# THS788_3.net
KiCad netlist of a schematic drawn in Altium Designer
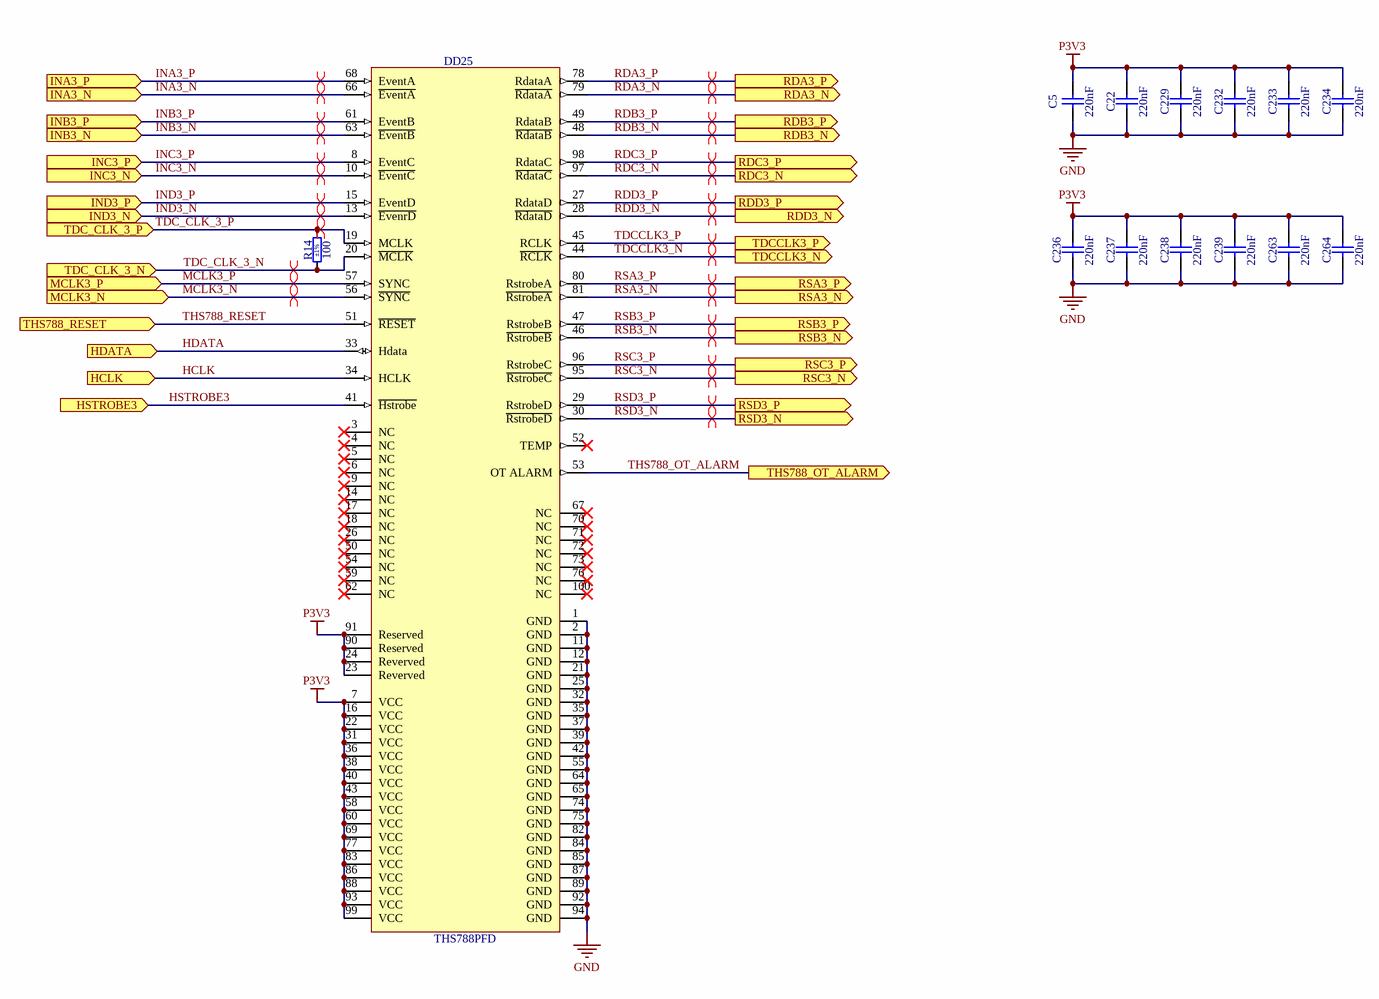
[diagram p0: THS788_3.SchDoc]

(export (version "E")
  (design (tool "Eeschema 10.0.6"))
  (components
    (comp (ref "C5")
      (value "220nF")
      (footprint "CAPC2012X135N")
      (description "Non-polarised capacitor")
      (fields
        (field (name "PART NUMBER") "CC0805_220NF_50V_10%_X7R")
        (field (name "VOLTAGE") "50V")
        (field (name "AUTHOR") "CERN DEM JLC")
      )
      (libsource (lib "Capacitors") (part "Capacitor - non polarized"))
    )
    (comp (ref "C22")
      (value "220nF")
      (footprint "CAPC2012X135N")
      (description "Non-polarised capacitor")
      (fields
        (field (name "PART NUMBER") "CC0805_220NF_50V_10%_X7R")
        (field (name "VOLTAGE") "50V")
        (field (name "AUTHOR") "CERN DEM JLC")
      )
      (libsource (lib "Capacitors") (part "Capacitor - non polarized"))
    )
    (comp (ref "C229")
      (value "220nF")
      (footprint "CAPC2012X135N")
      (description "Non-polarised capacitor")
      (fields
        (field (name "PART NUMBER") "CC0805_220NF_50V_10%_X7R")
        (field (name "VOLTAGE") "50V")
        (field (name "AUTHOR") "CERN DEM JLC")
      )
      (libsource (lib "Capacitors") (part "Capacitor - non polarized"))
    )
    (comp (ref "C232")
      (value "220nF")
      (footprint "CAPC2012X135N")
      (description "Non-polarised capacitor")
      (fields
        (field (name "PART NUMBER") "CC0805_220NF_50V_10%_X7R")
        (field (name "VOLTAGE") "50V")
        (field (name "AUTHOR") "CERN DEM JLC")
      )
      (libsource (lib "Capacitors") (part "Capacitor - non polarized"))
    )
    (comp (ref "C233")
      (value "220nF")
      (footprint "CAPC2012X135N")
      (description "Non-polarised capacitor")
      (fields
        (field (name "PART NUMBER") "CC0805_220NF_50V_10%_X7R")
        (field (name "VOLTAGE") "50V")
        (field (name "AUTHOR") "CERN DEM JLC")
      )
      (libsource (lib "Capacitors") (part "Capacitor - non polarized"))
    )
    (comp (ref "C234")
      (value "220nF")
      (footprint "CAPC2012X135N")
      (description "Non-polarised capacitor")
      (fields
        (field (name "PART NUMBER") "CC0805_220NF_50V_10%_X7R")
        (field (name "VOLTAGE") "50V")
        (field (name "AUTHOR") "CERN DEM JLC")
      )
      (libsource (lib "Capacitors") (part "Capacitor - non polarized"))
    )
    (comp (ref "C236")
      (value "220nF")
      (footprint "CAPC2012X135N")
      (description "Non-polarised capacitor")
      (fields
        (field (name "PART NUMBER") "CC0805_220NF_50V_10%_X7R")
        (field (name "VOLTAGE") "50V")
        (field (name "AUTHOR") "CERN DEM JLC")
      )
      (libsource (lib "Capacitors") (part "Capacitor - non polarized"))
    )
    (comp (ref "C237")
      (value "220nF")
      (footprint "CAPC2012X135N")
      (description "Non-polarised capacitor")
      (fields
        (field (name "PART NUMBER") "CC0805_220NF_50V_10%_X7R")
        (field (name "VOLTAGE") "50V")
        (field (name "AUTHOR") "CERN DEM JLC")
      )
      (libsource (lib "Capacitors") (part "Capacitor - non polarized"))
    )
    (comp (ref "C238")
      (value "220nF")
      (footprint "CAPC2012X135N")
      (description "Non-polarised capacitor")
      (fields
        (field (name "PART NUMBER") "CC0805_220NF_50V_10%_X7R")
        (field (name "VOLTAGE") "50V")
        (field (name "AUTHOR") "CERN DEM JLC")
      )
      (libsource (lib "Capacitors") (part "Capacitor - non polarized"))
    )
    (comp (ref "C239")
      (value "220nF")
      (footprint "CAPC2012X135N")
      (description "Non-polarised capacitor")
      (fields
        (field (name "PART NUMBER") "CC0805_220NF_50V_10%_X7R")
        (field (name "VOLTAGE") "50V")
        (field (name "AUTHOR") "CERN DEM JLC")
      )
      (libsource (lib "Capacitors") (part "Capacitor - non polarized"))
    )
    (comp (ref "C263")
      (value "220nF")
      (footprint "CAPC2012X135N")
      (description "Non-polarised capacitor")
      (fields
        (field (name "PART NUMBER") "CC0805_220NF_50V_10%_X7R")
        (field (name "VOLTAGE") "50V")
        (field (name "AUTHOR") "CERN DEM JLC")
      )
      (libsource (lib "Capacitors") (part "Capacitor - non polarized"))
    )
    (comp (ref "C264")
      (value "220nF")
      (footprint "CAPC2012X135N")
      (description "Non-polarised capacitor")
      (fields
        (field (name "PART NUMBER") "CC0805_220NF_50V_10%_X7R")
        (field (name "VOLTAGE") "50V")
        (field (name "AUTHOR") "CERN DEM JLC")
      )
      (libsource (lib "Capacitors") (part "Capacitor - non polarized"))
    )
    (comp (ref "DD25")
      (value "THS788PFD")
      (footprint "TEXAS_PFD (S-PQFP-G100)")
      (description "Quad-Channel Time Measurement Unit (TMU)")
      (fields (field (name "MANUFACTURER") "TEXAS INSTRUMENTS") (field (name "AUTHOR") "CERN DEM HF"))
      (libsource (lib "ICs And Semiconductors") (part "THS788PFD"))
    )
    (comp (ref "R14")
      (value "100")
      (footprint "RESC1608X55N")
      (description "Resistor - 1%")
      (fields
        (field (name "TOLERANCE") "±1%")
        (field (name "PART NUMBER") "R0603_100R_1%_0.1W_100PPM")
        (field (name "POWER") "0.1W")
        (field (name "AUTHOR") "CERN DEM JLC")
      )
      (libsource (lib "Resistors") (part "Resistor - 1%"))
    )
  )
  (nets
    (net (code "1") (name "/HCLK") (class "Default")
      (node (ref "DD25") (pin "34") (pinfunction "HCLK_34") (pintype "input"))
    )
    (net (code "2") (name "/HDATA") (class "Default")
      (node (ref "DD25") (pin "33") (pinfunction "Hdata_33") (pintype "bidirectional"))
    )
    (net (code "3") (name "/HSTROBE3") (class "Default")
      (node (ref "DD25") (pin "41") (pinfunction "~{Hstrobe}_41") (pintype "input"))
    )
    (net (code "4") (name "/INA3_N") (class "Default")
      (node (ref "DD25") (pin "66") (pinfunction "~{EventA}_66") (pintype "input"))
    )
    (net (code "5") (name "/INA3_P") (class "Default")
      (node (ref "DD25") (pin "68") (pinfunction "EventA_68") (pintype "input"))
    )
    (net (code "6") (name "/INB3_N") (class "Default")
      (node (ref "DD25") (pin "63") (pinfunction "~{EventB}_63") (pintype "input"))
    )
    (net (code "7") (name "/INB3_P") (class "Default")
      (node (ref "DD25") (pin "61") (pinfunction "EventB_61") (pintype "input"))
    )
    (net (code "8") (name "/INC3_N") (class "Default")
      (node (ref "DD25") (pin "10") (pinfunction "~{EventC}_10") (pintype "input"))
    )
    (net (code "9") (name "/INC3_P") (class "Default")
      (node (ref "DD25") (pin "8") (pinfunction "EventC_8") (pintype "input"))
    )
    (net (code "10") (name "/IND3_N") (class "Default")
      (node (ref "DD25") (pin "13") (pinfunction "~{EvenrD}_13") (pintype "input"))
    )
    (net (code "11") (name "/IND3_P") (class "Default")
      (node (ref "DD25") (pin "15") (pinfunction "EventD_15") (pintype "input"))
    )
    (net (code "12") (name "/MCLK3_N") (class "Default")
      (node (ref "DD25") (pin "56") (pinfunction "~{SYNC}_56") (pintype "input"))
    )
    (net (code "13") (name "/MCLK3_P") (class "Default")
      (node (ref "DD25") (pin "57") (pinfunction "SYNC_57") (pintype "input"))
    )
    (net (code "14") (name "/RDA3_N") (class "Default")
      (node (ref "DD25") (pin "79") (pinfunction "~{RdataA}_79") (pintype "output"))
    )
    (net (code "15") (name "/RDA3_P") (class "Default")
      (node (ref "DD25") (pin "78") (pinfunction "RdataA_78") (pintype "output"))
    )
    (net (code "16") (name "/RDB3_N") (class "Default")
      (node (ref "DD25") (pin "48") (pinfunction "~{RdataB}_48") (pintype "output"))
    )
    (net (code "17") (name "/RDB3_P") (class "Default")
      (node (ref "DD25") (pin "49") (pinfunction "RdataB_49") (pintype "output"))
    )
    (net (code "18") (name "/RDC3_N") (class "Default")
      (node (ref "DD25") (pin "97") (pinfunction "~{RdataC}_97") (pintype "output"))
    )
    (net (code "19") (name "/RDC3_P") (class "Default")
      (node (ref "DD25") (pin "98") (pinfunction "RdataC_98") (pintype "output"))
    )
    (net (code "20") (name "/RDD3_N") (class "Default")
      (node (ref "DD25") (pin "28") (pinfunction "~{RdataD}_28") (pintype "output"))
    )
    (net (code "21") (name "/RDD3_P") (class "Default")
      (node (ref "DD25") (pin "27") (pinfunction "RdataD_27") (pintype "output"))
    )
    (net (code "22") (name "/RSA3_N") (class "Default")
      (node (ref "DD25") (pin "81") (pinfunction "~{RstrobeA}_81") (pintype "output"))
    )
    (net (code "23") (name "/RSA3_P") (class "Default")
      (node (ref "DD25") (pin "80") (pinfunction "RstrobeA_80") (pintype "output"))
    )
    (net (code "24") (name "/RSB3_N") (class "Default")
      (node (ref "DD25") (pin "46") (pinfunction "~{RstrobeB}_46") (pintype "output"))
    )
    (net (code "25") (name "/RSB3_P") (class "Default")
      (node (ref "DD25") (pin "47") (pinfunction "RstrobeB_47") (pintype "output"))
    )
    (net (code "26") (name "/RSC3_N") (class "Default")
      (node (ref "DD25") (pin "95") (pinfunction "~{RstrobeC}_95") (pintype "output"))
    )
    (net (code "27") (name "/RSC3_P") (class "Default")
      (node (ref "DD25") (pin "96") (pinfunction "RstrobeC_96") (pintype "output"))
    )
    (net (code "28") (name "/RSD3_N") (class "Default")
      (node (ref "DD25") (pin "30") (pinfunction "~{RstrobeD}_30") (pintype "output"))
    )
    (net (code "29") (name "/RSD3_P") (class "Default")
      (node (ref "DD25") (pin "29") (pinfunction "RstrobeD_29") (pintype "output"))
    )
    (net (code "30") (name "/TDCCLK3_N") (class "Default")
      (node (ref "DD25") (pin "44") (pinfunction "~{RCLK}_44") (pintype "output"))
    )
    (net (code "31") (name "/TDCCLK3_P") (class "Default")
      (node (ref "DD25") (pin "45") (pinfunction "RCLK_45") (pintype "output"))
    )
    (net (code "32") (name "/TDC_CLK_3_N") (class "Default")
      (node (ref "DD25") (pin "20") (pinfunction "~{MCLK}_20") (pintype "input"))
      (node (ref "R14") (pin "1") (pinfunction "1_1") (pintype "passive"))
    )
    (net (code "33") (name "/TDC_CLK_3_P") (class "Default")
      (node (ref "DD25") (pin "19") (pinfunction "MCLK_19") (pintype "input"))
      (node (ref "R14") (pin "2") (pinfunction "2_2") (pintype "passive"))
    )
    (net (code "34") (name "/THS788_OT_ALARM") (class "Default")
      (node (ref "DD25") (pin "53") (pinfunction "OT_ALARM_53") (pintype "output"))
    )
    (net (code "35") (name "/THS788_RESET") (class "Default")
      (node (ref "DD25") (pin "51") (pinfunction "~{RESET}_51") (pintype "input"))
    )
    (net (code "36") (name "GND") (class "Default")
      (node (ref "C22") (pin "1") (pinfunction "1_1") (pintype "passive"))
      (node (ref "C229") (pin "1") (pinfunction "1_1") (pintype "passive"))
      (node (ref "C232") (pin "1") (pinfunction "1_1") (pintype "passive"))
      (node (ref "C233") (pin "1") (pinfunction "1_1") (pintype "passive"))
      (node (ref "C234") (pin "1") (pinfunction "1_1") (pintype "passive"))
      (node (ref "C236") (pin "1") (pinfunction "1_1") (pintype "passive"))
      (node (ref "C237") (pin "1") (pinfunction "1_1") (pintype "passive"))
      (node (ref "C238") (pin "1") (pinfunction "1_1") (pintype "passive"))
      (node (ref "C239") (pin "1") (pinfunction "1_1") (pintype "passive"))
      (node (ref "C263") (pin "1") (pinfunction "1_1") (pintype "passive"))
      (node (ref "C264") (pin "1") (pinfunction "1_1") (pintype "passive"))
      (node (ref "C5") (pin "1") (pinfunction "1_1") (pintype "passive"))
      (node (ref "DD25") (pin "1") (pinfunction "GND_1") (pintype "power_in"))
      (node (ref "DD25") (pin "11") (pinfunction "GND_11") (pintype "power_in"))
      (node (ref "DD25") (pin "12") (pinfunction "GND_12") (pintype "power_in"))
      (node (ref "DD25") (pin "2") (pinfunction "GND_2") (pintype "power_in"))
      (node (ref "DD25") (pin "21") (pinfunction "GND_21") (pintype "power_in"))
      (node (ref "DD25") (pin "25") (pinfunction "GND_25") (pintype "power_in"))
      (node (ref "DD25") (pin "32") (pinfunction "GND_32") (pintype "power_in"))
      (node (ref "DD25") (pin "35") (pinfunction "GND_35") (pintype "power_in"))
      (node (ref "DD25") (pin "37") (pinfunction "GND_37") (pintype "power_in"))
      (node (ref "DD25") (pin "39") (pinfunction "GND_39") (pintype "power_in"))
      (node (ref "DD25") (pin "42") (pinfunction "GND_42") (pintype "power_in"))
      (node (ref "DD25") (pin "55") (pinfunction "GND_55") (pintype "power_in"))
      (node (ref "DD25") (pin "64") (pinfunction "GND_64") (pintype "power_in"))
      (node (ref "DD25") (pin "65") (pinfunction "GND_65") (pintype "power_in"))
      (node (ref "DD25") (pin "74") (pinfunction "GND_74") (pintype "power_in"))
      (node (ref "DD25") (pin "75") (pinfunction "GND_75") (pintype "power_in"))
      (node (ref "DD25") (pin "82") (pinfunction "GND_82") (pintype "power_in"))
      (node (ref "DD25") (pin "84") (pinfunction "GND_84") (pintype "power_in"))
      (node (ref "DD25") (pin "85") (pinfunction "GND_85") (pintype "power_in"))
      (node (ref "DD25") (pin "87") (pinfunction "GND_87") (pintype "power_in"))
      (node (ref "DD25") (pin "89") (pinfunction "GND_89") (pintype "power_in"))
      (node (ref "DD25") (pin "92") (pinfunction "GND_92") (pintype "power_in"))
      (node (ref "DD25") (pin "94") (pinfunction "GND_94") (pintype "power_in"))
    )
    (net (code "37") (name "P3V3") (class "Default")
      (node (ref "C22") (pin "2") (pinfunction "2_2") (pintype "passive"))
      (node (ref "C229") (pin "2") (pinfunction "2_2") (pintype "passive"))
      (node (ref "C232") (pin "2") (pinfunction "2_2") (pintype "passive"))
      (node (ref "C233") (pin "2") (pinfunction "2_2") (pintype "passive"))
      (node (ref "C234") (pin "2") (pinfunction "2_2") (pintype "passive"))
      (node (ref "C236") (pin "2") (pinfunction "2_2") (pintype "passive"))
      (node (ref "C237") (pin "2") (pinfunction "2_2") (pintype "passive"))
      (node (ref "C238") (pin "2") (pinfunction "2_2") (pintype "passive"))
      (node (ref "C239") (pin "2") (pinfunction "2_2") (pintype "passive"))
      (node (ref "C263") (pin "2") (pinfunction "2_2") (pintype "passive"))
      (node (ref "C264") (pin "2") (pinfunction "2_2") (pintype "passive"))
      (node (ref "C5") (pin "2") (pinfunction "2_2") (pintype "passive"))
      (node (ref "DD25") (pin "16") (pinfunction "VCC_16") (pintype "power_in"))
      (node (ref "DD25") (pin "22") (pinfunction "VCC_22") (pintype "power_in"))
      (node (ref "DD25") (pin "23") (pinfunction "Reverved_23") (pintype "passive"))
      (node (ref "DD25") (pin "24") (pinfunction "Reverved_24") (pintype "passive"))
      (node (ref "DD25") (pin "31") (pinfunction "VCC_31") (pintype "power_in"))
      (node (ref "DD25") (pin "36") (pinfunction "VCC_36") (pintype "power_in"))
      (node (ref "DD25") (pin "38") (pinfunction "VCC_38") (pintype "power_in"))
      (node (ref "DD25") (pin "40") (pinfunction "VCC_40") (pintype "power_in"))
      (node (ref "DD25") (pin "43") (pinfunction "VCC_43") (pintype "power_in"))
      (node (ref "DD25") (pin "58") (pinfunction "VCC_58") (pintype "power_in"))
      (node (ref "DD25") (pin "60") (pinfunction "VCC_60") (pintype "power_in"))
      (node (ref "DD25") (pin "69") (pinfunction "VCC_69") (pintype "power_in"))
      (node (ref "DD25") (pin "7") (pinfunction "VCC_7") (pintype "power_in"))
      (node (ref "DD25") (pin "77") (pinfunction "VCC_77") (pintype "power_in"))
      (node (ref "DD25") (pin "83") (pinfunction "VCC_83") (pintype "power_in"))
      (node (ref "DD25") (pin "86") (pinfunction "VCC_86") (pintype "power_in"))
      (node (ref "DD25") (pin "88") (pinfunction "VCC_88") (pintype "power_in"))
      (node (ref "DD25") (pin "90") (pinfunction "Reserved_90") (pintype "passive"))
      (node (ref "DD25") (pin "91") (pinfunction "Reserved_91") (pintype "passive"))
      (node (ref "DD25") (pin "93") (pinfunction "VCC_93") (pintype "power_in"))
      (node (ref "DD25") (pin "99") (pinfunction "VCC_99") (pintype "power_in"))
    )
    (net (code "38") (name "unconnected-(DD25-NC-Pad3)") (class "Default")
      (node (ref "DD25") (pin "3") (pinfunction "NC_3") (pintype "passive+no_connect"))
    )
    (net (code "39") (name "unconnected-(DD25-NC-Pad4)") (class "Default")
      (node (ref "DD25") (pin "4") (pinfunction "NC_4") (pintype "passive+no_connect"))
    )
    (net (code "40") (name "unconnected-(DD25-NC-Pad5)") (class "Default")
      (node (ref "DD25") (pin "5") (pinfunction "NC_5") (pintype "passive+no_connect"))
    )
    (net (code "41") (name "unconnected-(DD25-NC-Pad6)") (class "Default")
      (node (ref "DD25") (pin "6") (pinfunction "NC_6") (pintype "passive+no_connect"))
    )
    (net (code "42") (name "unconnected-(DD25-NC-Pad9)") (class "Default")
      (node (ref "DD25") (pin "9") (pinfunction "NC_9") (pintype "passive+no_connect"))
    )
    (net (code "43") (name "unconnected-(DD25-NC-Pad14)") (class "Default")
      (node (ref "DD25") (pin "14") (pinfunction "NC_14") (pintype "passive+no_connect"))
    )
    (net (code "44") (name "unconnected-(DD25-NC-Pad17)") (class "Default")
      (node (ref "DD25") (pin "17") (pinfunction "NC_17") (pintype "passive+no_connect"))
    )
    (net (code "45") (name "unconnected-(DD25-NC-Pad18)") (class "Default")
      (node (ref "DD25") (pin "18") (pinfunction "NC_18") (pintype "passive+no_connect"))
    )
    (net (code "46") (name "unconnected-(DD25-NC-Pad26)") (class "Default")
      (node (ref "DD25") (pin "26") (pinfunction "NC_26") (pintype "passive+no_connect"))
    )
    (net (code "47") (name "unconnected-(DD25-NC-Pad50)") (class "Default")
      (node (ref "DD25") (pin "50") (pinfunction "NC_50") (pintype "passive+no_connect"))
    )
    (net (code "48") (name "unconnected-(DD25-NC-Pad54)") (class "Default")
      (node (ref "DD25") (pin "54") (pinfunction "NC_54") (pintype "passive+no_connect"))
    )
    (net (code "49") (name "unconnected-(DD25-NC-Pad59)") (class "Default")
      (node (ref "DD25") (pin "59") (pinfunction "NC_59") (pintype "passive+no_connect"))
    )
    (net (code "50") (name "unconnected-(DD25-NC-Pad62)") (class "Default")
      (node (ref "DD25") (pin "62") (pinfunction "NC_62") (pintype "passive+no_connect"))
    )
    (net (code "51") (name "unconnected-(DD25-NC-Pad67)") (class "Default")
      (node (ref "DD25") (pin "67") (pinfunction "NC_67") (pintype "passive+no_connect"))
    )
    (net (code "52") (name "unconnected-(DD25-NC-Pad70)") (class "Default")
      (node (ref "DD25") (pin "70") (pinfunction "NC_70") (pintype "passive+no_connect"))
    )
    (net (code "53") (name "unconnected-(DD25-NC-Pad71)") (class "Default")
      (node (ref "DD25") (pin "71") (pinfunction "NC_71") (pintype "passive+no_connect"))
    )
    (net (code "54") (name "unconnected-(DD25-NC-Pad72)") (class "Default")
      (node (ref "DD25") (pin "72") (pinfunction "NC_72") (pintype "passive+no_connect"))
    )
    (net (code "55") (name "unconnected-(DD25-NC-Pad73)") (class "Default")
      (node (ref "DD25") (pin "73") (pinfunction "NC_73") (pintype "passive+no_connect"))
    )
    (net (code "56") (name "unconnected-(DD25-NC-Pad76)") (class "Default")
      (node (ref "DD25") (pin "76") (pinfunction "NC_76") (pintype "passive+no_connect"))
    )
    (net (code "57") (name "unconnected-(DD25-NC-Pad100)") (class "Default")
      (node (ref "DD25") (pin "100") (pinfunction "NC_100") (pintype "passive+no_connect"))
    )
    (net (code "58") (name "unconnected-(DD25-TEMP-Pad52)") (class "Default")
      (node (ref "DD25") (pin "52") (pinfunction "TEMP_52") (pintype "output+no_connect"))
    )
  )
)
